# odr1_redraw.net
KiCad netlist of a schematic drawn in EAGLE
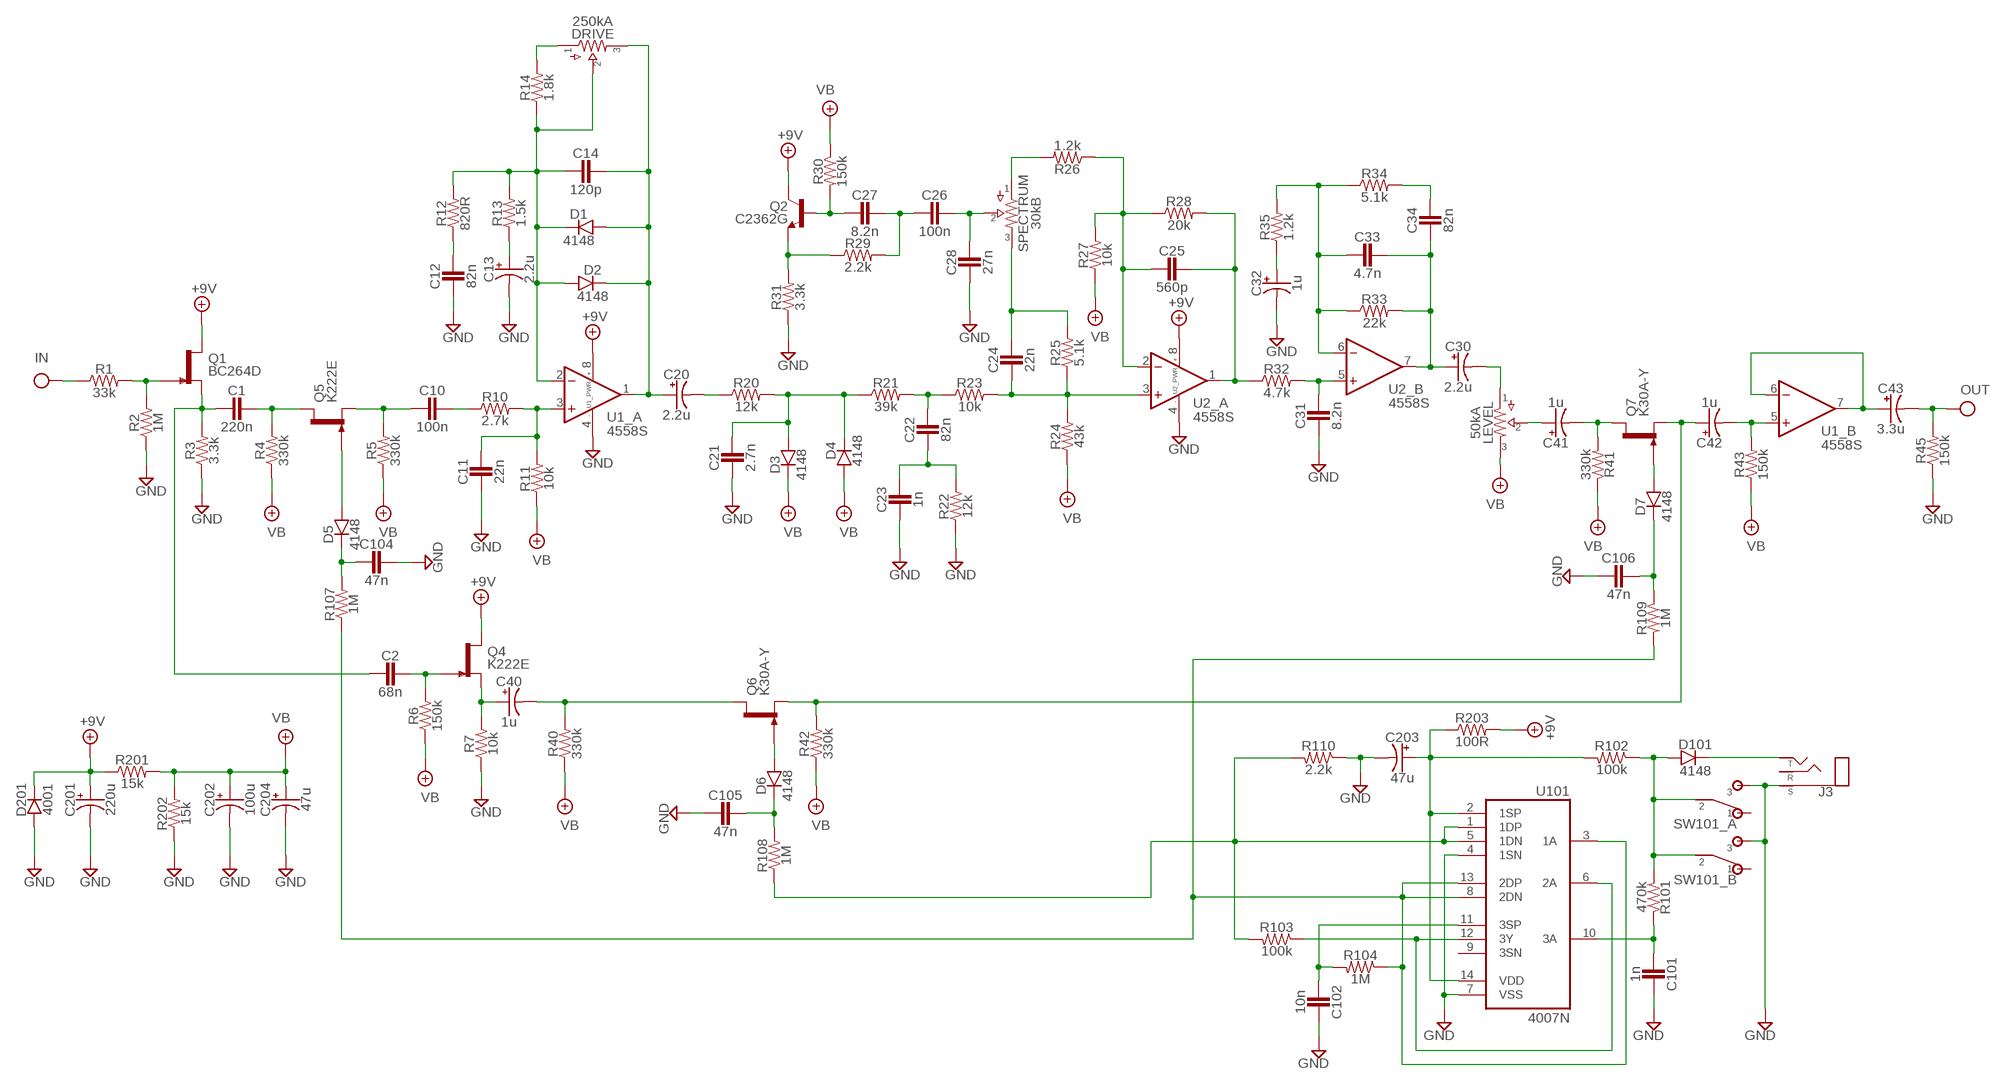
[diagram p0: schematic, sheet 1]

(export (version "E")
  (design (tool "Eeschema 10.0.6"))
  (components
    (comp (ref "C1")
      (value "220n")
      (footprint "eagle-import:BOX_SMALL")
      (libsource (lib "eagle-import") (part "CER/FILMBOX.1"))
    )
    (comp (ref "C2")
      (value "68n")
      (footprint "eagle-import:BOX_SMALL")
      (libsource (lib "eagle-import") (part "CER/FILMBOX.1"))
    )
    (comp (ref "C10")
      (value "100n")
      (footprint "eagle-import:BOX_SMALL")
      (libsource (lib "eagle-import") (part "CER/FILMBOX.1"))
    )
    (comp (ref "C11")
      (value "22n")
      (footprint "eagle-import:BOX_SMALL")
      (libsource (lib "eagle-import") (part "CER/FILMBOX.1"))
    )
    (comp (ref "C12")
      (value "82n")
      (footprint "eagle-import:BOX_SMALL")
      (libsource (lib "eagle-import") (part "CER/FILMBOX.1"))
    )
    (comp (ref "C13")
      (value "2.2u")
      (footprint "eagle-import:040_020")
      (libsource (lib "eagle-import") (part "0400"))
    )
    (comp (ref "C14")
      (value "120p")
      (footprint "eagle-import:BOX_SMALL")
      (libsource (lib "eagle-import") (part "CER/FILMBOX.1"))
    )
    (comp (ref "C20")
      (value "2.2u")
      (footprint "eagle-import:040_020")
      (libsource (lib "eagle-import") (part "0400"))
    )
    (comp (ref "C21")
      (value "2.7n")
      (footprint "eagle-import:BOX_SMALL")
      (libsource (lib "eagle-import") (part "CER/FILMBOX.1"))
    )
    (comp (ref "C22")
      (value "82n")
      (footprint "eagle-import:BOX_SMALL")
      (libsource (lib "eagle-import") (part "CER/FILMBOX.1"))
    )
    (comp (ref "C23")
      (value "1n")
      (footprint "eagle-import:BOX_SMALL")
      (libsource (lib "eagle-import") (part "CER/FILMBOX.1"))
    )
    (comp (ref "C24")
      (value "22n")
      (footprint "eagle-import:BOX_SMALL")
      (libsource (lib "eagle-import") (part "CER/FILMBOX.1"))
    )
    (comp (ref "C25")
      (value "560p")
      (footprint "eagle-import:BOX_SMALL")
      (libsource (lib "eagle-import") (part "CER/FILMBOX.1"))
    )
    (comp (ref "C26")
      (value "100n")
      (footprint "eagle-import:BOX_SMALL")
      (libsource (lib "eagle-import") (part "CER/FILMBOX.1"))
    )
    (comp (ref "C27")
      (value "8.2n")
      (footprint "eagle-import:BOX_SMALL")
      (libsource (lib "eagle-import") (part "CER/FILMBOX.1"))
    )
    (comp (ref "C28")
      (value "27n")
      (footprint "eagle-import:BOX_SMALL")
      (libsource (lib "eagle-import") (part "CER/FILMBOX.1"))
    )
    (comp (ref "C30")
      (value "2.2u")
      (footprint "eagle-import:040_020")
      (libsource (lib "eagle-import") (part "0400"))
    )
    (comp (ref "C31")
      (value "8.2n")
      (footprint "eagle-import:BOX_SMALL")
      (libsource (lib "eagle-import") (part "CER/FILMBOX.1"))
    )
    (comp (ref "C32")
      (value "1u")
      (footprint "eagle-import:040_020")
      (libsource (lib "eagle-import") (part "0400"))
    )
    (comp (ref "C33")
      (value "4.7n")
      (footprint "eagle-import:BOX_SMALL")
      (libsource (lib "eagle-import") (part "CER/FILMBOX.1"))
    )
    (comp (ref "C34")
      (value "82n")
      (footprint "eagle-import:BOX_SMALL")
      (libsource (lib "eagle-import") (part "CER/FILMBOX.1"))
    )
    (comp (ref "C40")
      (value "1u")
      (footprint "eagle-import:040_020")
      (libsource (lib "eagle-import") (part "0400"))
    )
    (comp (ref "C41")
      (value "1u")
      (footprint "eagle-import:040_020")
      (libsource (lib "eagle-import") (part "0400"))
    )
    (comp (ref "C42")
      (value "1u")
      (footprint "eagle-import:040_020")
      (libsource (lib "eagle-import") (part "0400"))
    )
    (comp (ref "C43")
      (value "3.3u")
      (footprint "eagle-import:040_020")
      (libsource (lib "eagle-import") (part "0400"))
    )
    (comp (ref "C101")
      (value "1n")
      (footprint "eagle-import:BOX_SMALL")
      (libsource (lib "eagle-import") (part "CER/FILMBOX.1"))
    )
    (comp (ref "C102")
      (value "10n")
      (footprint "eagle-import:BOX_SMALL")
      (libsource (lib "eagle-import") (part "CER/FILMBOX.1"))
    )
    (comp (ref "C104")
      (value "47n")
      (footprint "eagle-import:BOX_SMALL")
      (libsource (lib "eagle-import") (part "CER/FILMBOX.1"))
    )
    (comp (ref "C105")
      (value "47n")
      (footprint "eagle-import:BOX_SMALL")
      (libsource (lib "eagle-import") (part "CER/FILMBOX.1"))
    )
    (comp (ref "C106")
      (value "47n")
      (footprint "eagle-import:BOX_SMALL")
      (libsource (lib "eagle-import") (part "CER/FILMBOX.1"))
    )
    (comp (ref "C201")
      (value "220u")
      (footprint "eagle-import:040_020")
      (libsource (lib "eagle-import") (part "0400"))
    )
    (comp (ref "C202")
      (value "100u")
      (footprint "eagle-import:040_020")
      (libsource (lib "eagle-import") (part "0400"))
    )
    (comp (ref "C203")
      (value "47u")
      (footprint "eagle-import:040_020")
      (libsource (lib "eagle-import") (part "0400"))
    )
    (comp (ref "C204")
      (value "47u")
      (footprint "eagle-import:040_020")
      (libsource (lib "eagle-import") (part "0400"))
    )
    (comp (ref "D1")
      (value "4148")
      (footprint "eagle-import:DO35-2")
      (libsource (lib "eagle-import") (part "DO35.2"))
    )
    (comp (ref "D2")
      (value "4148")
      (footprint "eagle-import:DO35-2")
      (libsource (lib "eagle-import") (part "DO35.2"))
    )
    (comp (ref "D3")
      (value "4148")
      (footprint "eagle-import:DO35-2")
      (libsource (lib "eagle-import") (part "DO35.2"))
    )
    (comp (ref "D4")
      (value "4148")
      (footprint "eagle-import:DO35-2")
      (libsource (lib "eagle-import") (part "DO35.2"))
    )
    (comp (ref "D5")
      (value "4148")
      (footprint "eagle-import:DO35-2")
      (libsource (lib "eagle-import") (part "DO35.2"))
    )
    (comp (ref "D6")
      (value "4148")
      (footprint "eagle-import:DO35-2")
      (libsource (lib "eagle-import") (part "DO35.2"))
    )
    (comp (ref "D7")
      (value "4148")
      (footprint "eagle-import:DO35-2")
      (libsource (lib "eagle-import") (part "DO35.2"))
    )
    (comp (ref "D101")
      (value "4148")
      (footprint "eagle-import:DO35-2")
      (libsource (lib "eagle-import") (part "DO35.2"))
    )
    (comp (ref "D201")
      (value "4001")
      (footprint "eagle-import:DO35-2")
      (libsource (lib "eagle-import") (part "DO35.2"))
    )
    (comp (ref "DRIVE")
      (value "250kA")
      (footprint "eagle-import:16MM")
      (libsource (lib "eagle-import") (part "POTS16MM"))
    )
    (comp (ref "J3")
      (value "STEREO3PADS")
      (footprint "eagle-import:THREEPADS")
      (libsource (lib "eagle-import") (part "STEREO3PADS"))
    )
    (comp (ref "LEVEL")
      (value "50kA")
      (footprint "eagle-import:16MM")
      (libsource (lib "eagle-import") (part "POTS16MM"))
    )
    (comp (ref "Q1")
      (value "BC264D")
      (footprint "eagle-import:TO92-")
      (libsource (lib "eagle-import") (part "2N3819TO-92S"))
    )
    (comp (ref "Q2")
      (value "C2362G")
      (footprint "eagle-import:TO92-")
      (libsource (lib "eagle-import") (part "2N3904"))
    )
    (comp (ref "Q4")
      (value "K222E")
      (footprint "eagle-import:TO92-")
      (libsource (lib "eagle-import") (part "2N3819TO-92S"))
    )
    (comp (ref "Q5")
      (value "K222E")
      (footprint "eagle-import:TO92-")
      (libsource (lib "eagle-import") (part "2N3819TO-92S"))
    )
    (comp (ref "Q6")
      (value "K30A-Y")
      (footprint "eagle-import:TO92-")
      (libsource (lib "eagle-import") (part "2N3819TO-92S"))
    )
    (comp (ref "Q7")
      (value "K30A-Y")
      (footprint "eagle-import:TO92-")
      (libsource (lib "eagle-import") (part "2N3819TO-92S"))
    )
    (comp (ref "R1")
      (value "33k")
      (footprint "eagle-import:R0207_3")
      (libsource (lib "eagle-import") (part "R_.3B"))
    )
    (comp (ref "R2")
      (value "1M")
      (footprint "eagle-import:R0207_3")
      (libsource (lib "eagle-import") (part "R_.3B"))
    )
    (comp (ref "R3")
      (value "3.3k")
      (footprint "eagle-import:R0207_3")
      (libsource (lib "eagle-import") (part "R_.3B"))
    )
    (comp (ref "R4")
      (value "330k")
      (footprint "eagle-import:R0207_3")
      (libsource (lib "eagle-import") (part "R_.3B"))
    )
    (comp (ref "R5")
      (value "330k")
      (footprint "eagle-import:R0207_3")
      (libsource (lib "eagle-import") (part "R_.3B"))
    )
    (comp (ref "R6")
      (value "150k")
      (footprint "eagle-import:R0207_3")
      (libsource (lib "eagle-import") (part "R_.3B"))
    )
    (comp (ref "R7")
      (value "10k")
      (footprint "eagle-import:R0207_3")
      (libsource (lib "eagle-import") (part "R_.3B"))
    )
    (comp (ref "R10")
      (value "2.7k")
      (footprint "eagle-import:R0207_3")
      (libsource (lib "eagle-import") (part "R_.3B"))
    )
    (comp (ref "R11")
      (value "10k")
      (footprint "eagle-import:R0207_3")
      (libsource (lib "eagle-import") (part "R_.3B"))
    )
    (comp (ref "R12")
      (value "820R")
      (footprint "eagle-import:R0207_3")
      (libsource (lib "eagle-import") (part "R_.3B"))
    )
    (comp (ref "R13")
      (value "1.5k")
      (footprint "eagle-import:R0207_3")
      (libsource (lib "eagle-import") (part "R_.3B"))
    )
    (comp (ref "R14")
      (value "1.8k")
      (footprint "eagle-import:R0207_3")
      (libsource (lib "eagle-import") (part "R_.3B"))
    )
    (comp (ref "R20")
      (value "12k")
      (footprint "eagle-import:R0207_3")
      (libsource (lib "eagle-import") (part "R_.3B"))
    )
    (comp (ref "R21")
      (value "39k")
      (footprint "eagle-import:R0207_3")
      (libsource (lib "eagle-import") (part "R_.3B"))
    )
    (comp (ref "R22")
      (value "12k")
      (footprint "eagle-import:R0207_3")
      (libsource (lib "eagle-import") (part "R_.3B"))
    )
    (comp (ref "R23")
      (value "10k")
      (footprint "eagle-import:R0207_3")
      (libsource (lib "eagle-import") (part "R_.3B"))
    )
    (comp (ref "R24")
      (value "43k")
      (footprint "eagle-import:R0207_3")
      (libsource (lib "eagle-import") (part "R_.3B"))
    )
    (comp (ref "R25")
      (value "5.1k")
      (footprint "eagle-import:R0207_3")
      (libsource (lib "eagle-import") (part "R_.3B"))
    )
    (comp (ref "R26")
      (value "1.2k")
      (footprint "eagle-import:R0207_3")
      (libsource (lib "eagle-import") (part "R_.3B"))
    )
    (comp (ref "R27")
      (value "10k")
      (footprint "eagle-import:R0207_3")
      (libsource (lib "eagle-import") (part "R_.3B"))
    )
    (comp (ref "R28")
      (value "20k")
      (footprint "eagle-import:R0207_3")
      (libsource (lib "eagle-import") (part "R_.3B"))
    )
    (comp (ref "R29")
      (value "2.2k")
      (footprint "eagle-import:R0207_3")
      (libsource (lib "eagle-import") (part "R_.3B"))
    )
    (comp (ref "R30")
      (value "150k")
      (footprint "eagle-import:R0207_3")
      (libsource (lib "eagle-import") (part "R_.3B"))
    )
    (comp (ref "R31")
      (value "3.3k")
      (footprint "eagle-import:R0207_3")
      (libsource (lib "eagle-import") (part "R_.3B"))
    )
    (comp (ref "R32")
      (value "4.7k")
      (footprint "eagle-import:R0207_3")
      (libsource (lib "eagle-import") (part "R_.3B"))
    )
    (comp (ref "R33")
      (value "22k")
      (footprint "eagle-import:R0207_3")
      (libsource (lib "eagle-import") (part "R_.3B"))
    )
    (comp (ref "R34")
      (value "5.1k")
      (footprint "eagle-import:R0207_3")
      (libsource (lib "eagle-import") (part "R_.3B"))
    )
    (comp (ref "R35")
      (value "1.2k")
      (footprint "eagle-import:R0207_3")
      (libsource (lib "eagle-import") (part "R_.3B"))
    )
    (comp (ref "R40")
      (value "330k")
      (footprint "eagle-import:R0207_3")
      (libsource (lib "eagle-import") (part "R_.3B"))
    )
    (comp (ref "R41")
      (value "330k")
      (footprint "eagle-import:R0207_3")
      (libsource (lib "eagle-import") (part "R_.3B"))
    )
    (comp (ref "R42")
      (value "330k")
      (footprint "eagle-import:R0207_3")
      (libsource (lib "eagle-import") (part "R_.3B"))
    )
    (comp (ref "R43")
      (value "150k")
      (footprint "eagle-import:R0207_3")
      (libsource (lib "eagle-import") (part "R_.3B"))
    )
    (comp (ref "R45")
      (value "150k")
      (footprint "eagle-import:R0207_3")
      (libsource (lib "eagle-import") (part "R_.3B"))
    )
    (comp (ref "R101")
      (value "470k")
      (footprint "eagle-import:R0207_3")
      (libsource (lib "eagle-import") (part "R_.3B"))
    )
    (comp (ref "R102")
      (value "100k")
      (footprint "eagle-import:R0207_3")
      (libsource (lib "eagle-import") (part "R_.3B"))
    )
    (comp (ref "R103")
      (value "100k")
      (footprint "eagle-import:R0207_3")
      (libsource (lib "eagle-import") (part "R_.3B"))
    )
    (comp (ref "R104")
      (value "1M")
      (footprint "eagle-import:R0207_3")
      (libsource (lib "eagle-import") (part "R_.3B"))
    )
    (comp (ref "R107")
      (value "1M")
      (footprint "eagle-import:R0207_3")
      (libsource (lib "eagle-import") (part "R_.3B"))
    )
    (comp (ref "R108")
      (value "1M")
      (footprint "eagle-import:R0207_3")
      (libsource (lib "eagle-import") (part "R_.3B"))
    )
    (comp (ref "R109")
      (value "1M")
      (footprint "eagle-import:R0207_3")
      (libsource (lib "eagle-import") (part "R_.3B"))
    )
    (comp (ref "R110")
      (value "2.2k")
      (footprint "eagle-import:R0207_3")
      (libsource (lib "eagle-import") (part "R_.3B"))
    )
    (comp (ref "R201")
      (value "15k")
      (footprint "eagle-import:R0207_3")
      (libsource (lib "eagle-import") (part "R_.3B"))
    )
    (comp (ref "R202")
      (value "15k")
      (footprint "eagle-import:R0207_3")
      (libsource (lib "eagle-import") (part "R_.3B"))
    )
    (comp (ref "R203")
      (value "100R")
      (footprint "eagle-import:R0207_3")
      (libsource (lib "eagle-import") (part "R_.3B"))
    )
    (comp (ref "SPECTRUM")
      (value "30kB")
      (footprint "eagle-import:16MM")
      (libsource (lib "eagle-import") (part "POTS16MM"))
    )
    (comp (ref "SW101")
      (value "DPDT")
      (footprint "eagle-import:DPDT")
      (libsource (lib "eagle-import") (part "DPDT"))
    )
    (comp (ref "U1")
      (value "4558S")
      (footprint "eagle-import:DIL0")
      (libsource (lib "eagle-import") (part "DUALTH"))
    )
    (comp (ref "U2")
      (value "4558S")
      (footprint "eagle-import:DIL0")
      (libsource (lib "eagle-import") (part "DUALTH"))
    )
    (comp (ref "U101")
      (value "4007N")
      (footprint "eagle-import:DIL14")
      (libsource (lib "eagle-import") (part "4007N"))
    )
  )
  (nets
    (net (code "1") (name "+9V") (class "Default")
      (node (ref "C201") (pin "+") (pinfunction "+_+") (pintype "passive"))
      (node (ref "D201") (pin "C") (pinfunction "C_C") (pintype "passive"))
      (node (ref "Q1") (pin "3") (pinfunction "D_3") (pintype "passive"))
      (node (ref "Q2") (pin "1") (pinfunction "C_1") (pintype "passive"))
      (node (ref "Q4") (pin "3") (pinfunction "D_3") (pintype "passive"))
      (node (ref "R201") (pin "1") (pinfunction "1_1") (pintype "passive"))
      (node (ref "R203") (pin "2") (pinfunction "2_2") (pintype "passive"))
      (node (ref "U1") (pin "8") (pinfunction "V+_8") (pintype "power_in"))
      (node (ref "U2") (pin "8") (pinfunction "V+_8") (pintype "power_in"))
    )
    (net (code "2") (name "GND") (class "Default")
      (node (ref "C101") (pin "2") (pinfunction "2_2") (pintype "passive"))
      (node (ref "C102") (pin "2") (pinfunction "2_2") (pintype "passive"))
      (node (ref "C104") (pin "2") (pinfunction "2_2") (pintype "passive"))
      (node (ref "C105") (pin "2") (pinfunction "2_2") (pintype "passive"))
      (node (ref "C106") (pin "2") (pinfunction "2_2") (pintype "passive"))
      (node (ref "C11") (pin "2") (pinfunction "2_2") (pintype "passive"))
      (node (ref "C12") (pin "2") (pinfunction "2_2") (pintype "passive"))
      (node (ref "C13") (pin "-") (pinfunction "-_-") (pintype "passive"))
      (node (ref "C201") (pin "-") (pinfunction "-_-") (pintype "passive"))
      (node (ref "C202") (pin "-") (pinfunction "-_-") (pintype "passive"))
      (node (ref "C203") (pin "-") (pinfunction "-_-") (pintype "passive"))
      (node (ref "C204") (pin "-") (pinfunction "-_-") (pintype "passive"))
      (node (ref "C21") (pin "2") (pinfunction "2_2") (pintype "passive"))
      (node (ref "C23") (pin "2") (pinfunction "2_2") (pintype "passive"))
      (node (ref "C28") (pin "2") (pinfunction "2_2") (pintype "passive"))
      (node (ref "C31") (pin "2") (pinfunction "2_2") (pintype "passive"))
      (node (ref "C32") (pin "-") (pinfunction "-_-") (pintype "passive"))
      (node (ref "D201") (pin "A") (pinfunction "A_A") (pintype "passive"))
      (node (ref "J3") (pin "SLEEVE") (pinfunction "S_SLEEVE") (pintype "passive"))
      (node (ref "R110") (pin "1") (pinfunction "1_1") (pintype "passive"))
      (node (ref "R2") (pin "1") (pinfunction "1_1") (pintype "passive"))
      (node (ref "R202") (pin "1") (pinfunction "1_1") (pintype "passive"))
      (node (ref "R22") (pin "1") (pinfunction "1_1") (pintype "passive"))
      (node (ref "R3") (pin "1") (pinfunction "1_1") (pintype "passive"))
      (node (ref "R31") (pin "1") (pinfunction "1_1") (pintype "passive"))
      (node (ref "R45") (pin "1") (pinfunction "1_1") (pintype "passive"))
      (node (ref "R7") (pin "1") (pinfunction "1_1") (pintype "passive"))
      (node (ref "SW101") (pin "A3") (pinfunction "3_A3") (pintype "passive"))
      (node (ref "SW101") (pin "B3") (pinfunction "3_B3") (pintype "passive"))
      (node (ref "U1") (pin "4") (pinfunction "V-_4") (pintype "power_in"))
      (node (ref "U101") (pin "4") (pinfunction "1SN_4") (pintype "open_collector"))
      (node (ref "U101") (pin "7") (pinfunction "VSS_7") (pintype "input"))
      (node (ref "U2") (pin "4") (pinfunction "V-_4") (pintype "power_in"))
    )
    (net (code "3") (name "IN") (class "Default")
      (node (ref "R1") (pin "1") (pinfunction "1_1") (pintype "passive"))
    )
    (net (code "4") (name "Net-(C10-Pad1)") (class "Default")
      (node (ref "C10") (pin "1") (pinfunction "1_1") (pintype "passive"))
      (node (ref "R10") (pin "1") (pinfunction "1_1") (pintype "passive"))
    )
    (net (code "5") (name "Net-(C12-Pad1)") (class "Default")
      (node (ref "C12") (pin "1") (pinfunction "1_1") (pintype "passive"))
      (node (ref "R12") (pin "1") (pinfunction "1_1") (pintype "passive"))
    )
    (net (code "6") (name "Net-(C13-Pad+)") (class "Default")
      (node (ref "C13") (pin "+") (pinfunction "+_+") (pintype "passive"))
      (node (ref "R13") (pin "1") (pinfunction "1_1") (pintype "passive"))
    )
    (net (code "7") (name "Net-(C20-Pad-)") (class "Default")
      (node (ref "C20") (pin "-") (pinfunction "-_-") (pintype "passive"))
      (node (ref "R20") (pin "1") (pinfunction "1_1") (pintype "passive"))
    )
    (net (code "8") (name "Net-(C21-Pad1)") (class "Default")
      (node (ref "C21") (pin "1") (pinfunction "1_1") (pintype "passive"))
      (node (ref "D3") (pin "A") (pinfunction "A_A") (pintype "passive"))
      (node (ref "D4") (pin "C") (pinfunction "C_C") (pintype "passive"))
      (node (ref "R20") (pin "2") (pinfunction "2_2") (pintype "passive"))
      (node (ref "R21") (pin "1") (pinfunction "1_1") (pintype "passive"))
    )
    (net (code "9") (name "Net-(C22-Pad1)") (class "Default")
      (node (ref "C22") (pin "1") (pinfunction "1_1") (pintype "passive"))
      (node (ref "R21") (pin "2") (pinfunction "2_2") (pintype "passive"))
      (node (ref "R23") (pin "1") (pinfunction "1_1") (pintype "passive"))
    )
    (net (code "10") (name "Net-(C22-Pad2)") (class "Default")
      (node (ref "C22") (pin "2") (pinfunction "2_2") (pintype "passive"))
      (node (ref "C23") (pin "1") (pinfunction "1_1") (pintype "passive"))
      (node (ref "R22") (pin "2") (pinfunction "2_2") (pintype "passive"))
    )
    (net (code "11") (name "Net-(C24-Pad1)") (class "Default")
      (node (ref "C24") (pin "1") (pinfunction "1_1") (pintype "passive"))
      (node (ref "R25") (pin "2") (pinfunction "2_2") (pintype "passive"))
      (node (ref "SPECTRUM") (pin "3") (pinfunction "3_3") (pintype "passive"))
    )
    (net (code "12") (name "Net-(C26-Pad1)") (class "Default")
      (node (ref "C26") (pin "1") (pinfunction "1_1") (pintype "passive"))
      (node (ref "C28") (pin "1") (pinfunction "1_1") (pintype "passive"))
      (node (ref "SPECTRUM") (pin "2") (pinfunction "2_2") (pintype "passive"))
    )
    (net (code "13") (name "Net-(C26-Pad2)") (class "Default")
      (node (ref "C26") (pin "2") (pinfunction "2_2") (pintype "passive"))
      (node (ref "C27") (pin "1") (pinfunction "1_1") (pintype "passive"))
      (node (ref "R29") (pin "2") (pinfunction "2_2") (pintype "passive"))
    )
    (net (code "14") (name "Net-(C30-Pad-)") (class "Default")
      (node (ref "C30") (pin "-") (pinfunction "-_-") (pintype "passive"))
      (node (ref "LEVEL") (pin "1") (pinfunction "1_1") (pintype "passive"))
    )
    (net (code "15") (name "Net-(C32-Pad+)") (class "Default")
      (node (ref "C32") (pin "+") (pinfunction "+_+") (pintype "passive"))
      (node (ref "R35") (pin "1") (pinfunction "1_1") (pintype "passive"))
    )
    (net (code "16") (name "Net-(C34-Pad1)") (class "Default")
      (node (ref "C34") (pin "1") (pinfunction "1_1") (pintype "passive"))
      (node (ref "R34") (pin "2") (pinfunction "2_2") (pintype "passive"))
    )
    (net (code "17") (name "Net-(C41-Pad+)") (class "Default")
      (node (ref "C41") (pin "+") (pinfunction "+_+") (pintype "passive"))
      (node (ref "LEVEL") (pin "2") (pinfunction "2_2") (pintype "passive"))
    )
    (net (code "18") (name "Net-(C104-Pad1)") (class "Default")
      (node (ref "C104") (pin "1") (pinfunction "1_1") (pintype "passive"))
      (node (ref "D5") (pin "C") (pinfunction "C_C") (pintype "passive"))
      (node (ref "R107") (pin "2") (pinfunction "2_2") (pintype "passive"))
    )
    (net (code "19") (name "Net-(C105-Pad1)") (class "Default")
      (node (ref "C105") (pin "1") (pinfunction "1_1") (pintype "passive"))
      (node (ref "D6") (pin "C") (pinfunction "C_C") (pintype "passive"))
      (node (ref "R108") (pin "2") (pinfunction "2_2") (pintype "passive"))
    )
    (net (code "20") (name "Net-(C106-Pad1)") (class "Default")
      (node (ref "C106") (pin "1") (pinfunction "1_1") (pintype "passive"))
      (node (ref "D7") (pin "C") (pinfunction "C_C") (pintype "passive"))
      (node (ref "R109") (pin "1") (pinfunction "1_1") (pintype "passive"))
    )
    (net (code "21") (name "Net-(DRIVE-Pad1)") (class "Default")
      (node (ref "DRIVE") (pin "1") (pinfunction "1_1") (pintype "passive"))
      (node (ref "R14") (pin "2") (pinfunction "2_2") (pintype "passive"))
    )
    (net (code "22") (name "Net-(J3-T)") (class "Default")
      (node (ref "D101") (pin "C") (pinfunction "C_C") (pintype "passive"))
      (node (ref "J3") (pin "TIP") (pinfunction "T_TIP") (pintype "passive"))
    )
    (net (code "23") (name "Net-(Q1-G)") (class "Default")
      (node (ref "Q1") (pin "2") (pinfunction "G_2") (pintype "passive"))
      (node (ref "R1") (pin "2") (pinfunction "2_2") (pintype "passive"))
      (node (ref "R2") (pin "2") (pinfunction "2_2") (pintype "passive"))
    )
    (net (code "24") (name "Net-(Q1-S)") (class "Default")
      (node (ref "C1") (pin "2") (pinfunction "2_2") (pintype "passive"))
      (node (ref "C2") (pin "2") (pinfunction "2_2") (pintype "passive"))
      (node (ref "Q1") (pin "1") (pinfunction "S_1") (pintype "passive"))
      (node (ref "R3") (pin "2") (pinfunction "2_2") (pintype "passive"))
    )
    (net (code "25") (name "Net-(Q2-B)") (class "Default")
      (node (ref "C27") (pin "2") (pinfunction "2_2") (pintype "passive"))
      (node (ref "Q2") (pin "2") (pinfunction "B_2") (pintype "passive"))
      (node (ref "R30") (pin "2") (pinfunction "2_2") (pintype "passive"))
    )
    (net (code "26") (name "Net-(Q2-E)") (class "Default")
      (node (ref "Q2") (pin "3") (pinfunction "E_3") (pintype "passive"))
      (node (ref "R29") (pin "1") (pinfunction "1_1") (pintype "passive"))
      (node (ref "R31") (pin "2") (pinfunction "2_2") (pintype "passive"))
    )
    (net (code "27") (name "Net-(Q4-G)") (class "Default")
      (node (ref "C2") (pin "1") (pinfunction "1_1") (pintype "passive"))
      (node (ref "Q4") (pin "2") (pinfunction "G_2") (pintype "passive"))
      (node (ref "R6") (pin "2") (pinfunction "2_2") (pintype "passive"))
    )
    (net (code "28") (name "Net-(Q4-S)") (class "Default")
      (node (ref "C40") (pin "+") (pinfunction "+_+") (pintype "passive"))
      (node (ref "Q4") (pin "1") (pinfunction "S_1") (pintype "passive"))
      (node (ref "R7") (pin "2") (pinfunction "2_2") (pintype "passive"))
    )
    (net (code "29") (name "Net-(Q5-D)") (class "Default")
      (node (ref "C1") (pin "1") (pinfunction "1_1") (pintype "passive"))
      (node (ref "Q5") (pin "3") (pinfunction "D_3") (pintype "passive"))
      (node (ref "R4") (pin "2") (pinfunction "2_2") (pintype "passive"))
    )
    (net (code "30") (name "Net-(Q5-G)") (class "Default")
      (node (ref "D5") (pin "A") (pinfunction "A_A") (pintype "passive"))
      (node (ref "Q5") (pin "2") (pinfunction "G_2") (pintype "passive"))
    )
    (net (code "31") (name "Net-(Q5-S)") (class "Default")
      (node (ref "C10") (pin "2") (pinfunction "2_2") (pintype "passive"))
      (node (ref "Q5") (pin "1") (pinfunction "S_1") (pintype "passive"))
      (node (ref "R5") (pin "2") (pinfunction "2_2") (pintype "passive"))
    )
    (net (code "32") (name "Net-(Q6-D)") (class "Default")
      (node (ref "C40") (pin "-") (pinfunction "-_-") (pintype "passive"))
      (node (ref "Q6") (pin "3") (pinfunction "D_3") (pintype "passive"))
      (node (ref "R40") (pin "2") (pinfunction "2_2") (pintype "passive"))
    )
    (net (code "33") (name "Net-(Q6-G)") (class "Default")
      (node (ref "D6") (pin "A") (pinfunction "A_A") (pintype "passive"))
      (node (ref "Q6") (pin "2") (pinfunction "G_2") (pintype "passive"))
    )
    (net (code "34") (name "Net-(Q6-S)") (class "Default")
      (node (ref "C42") (pin "+") (pinfunction "+_+") (pintype "passive"))
      (node (ref "Q6") (pin "1") (pinfunction "S_1") (pintype "passive"))
      (node (ref "Q7") (pin "1") (pinfunction "S_1") (pintype "passive"))
      (node (ref "R42") (pin "2") (pinfunction "2_2") (pintype "passive"))
    )
    (net (code "35") (name "Net-(Q7-D)") (class "Default")
      (node (ref "C41") (pin "-") (pinfunction "-_-") (pintype "passive"))
      (node (ref "Q7") (pin "3") (pinfunction "D_3") (pintype "passive"))
      (node (ref "R41") (pin "2") (pinfunction "2_2") (pintype "passive"))
    )
    (net (code "36") (name "Net-(Q7-G)") (class "Default")
      (node (ref "D7") (pin "A") (pinfunction "A_A") (pintype "passive"))
      (node (ref "Q7") (pin "2") (pinfunction "G_2") (pintype "passive"))
    )
    (net (code "37") (name "Net-(R26-Pad2)") (class "Default")
      (node (ref "R26") (pin "2") (pinfunction "2_2") (pintype "passive"))
      (node (ref "SPECTRUM") (pin "1") (pinfunction "1_1") (pintype "passive"))
    )
    (net (code "38") (name "Net-(SW101A-2)") (class "Default")
      (node (ref "D101") (pin "A") (pinfunction "A_A") (pintype "passive"))
      (node (ref "R101") (pin "2") (pinfunction "2_2") (pintype "passive"))
      (node (ref "R102") (pin "1") (pinfunction "1_1") (pintype "passive"))
      (node (ref "SW101") (pin "A2") (pinfunction "2_A2") (pintype "passive"))
      (node (ref "SW101") (pin "B2") (pinfunction "2_B2") (pintype "passive"))
    )
    (net (code "39") (name "Net-(U1A-+IN)") (class "Default")
      (node (ref "C11") (pin "1") (pinfunction "1_1") (pintype "passive"))
      (node (ref "R10") (pin "2") (pinfunction "2_2") (pintype "passive"))
      (node (ref "R11") (pin "2") (pinfunction "2_2") (pintype "passive"))
      (node (ref "U1") (pin "3") (pinfunction "+IN_3") (pintype "input"))
    )
    (net (code "40") (name "Net-(U1A--IN)") (class "Default")
      (node (ref "C14") (pin "2") (pinfunction "2_2") (pintype "passive"))
      (node (ref "D1") (pin "C") (pinfunction "C_C") (pintype "passive"))
      (node (ref "D2") (pin "A") (pinfunction "A_A") (pintype "passive"))
      (node (ref "DRIVE") (pin "2") (pinfunction "2_2") (pintype "passive"))
      (node (ref "R12") (pin "2") (pinfunction "2_2") (pintype "passive"))
      (node (ref "R13") (pin "2") (pinfunction "2_2") (pintype "passive"))
      (node (ref "R14") (pin "1") (pinfunction "1_1") (pintype "passive"))
      (node (ref "U1") (pin "2") (pinfunction "-IN_2") (pintype "input"))
    )
    (net (code "41") (name "Net-(U1A-OUT)") (class "Default")
      (node (ref "C14") (pin "1") (pinfunction "1_1") (pintype "passive"))
      (node (ref "C20") (pin "+") (pinfunction "+_+") (pintype "passive"))
      (node (ref "D1") (pin "A") (pinfunction "A_A") (pintype "passive"))
      (node (ref "D2") (pin "C") (pinfunction "C_C") (pintype "passive"))
      (node (ref "DRIVE") (pin "3") (pinfunction "3_3") (pintype "passive"))
      (node (ref "U1") (pin "1") (pinfunction "OUT_1") (pintype "output"))
    )
    (net (code "42") (name "Net-(U1B-+IN)") (class "Default")
      (node (ref "C42") (pin "-") (pinfunction "-_-") (pintype "passive"))
      (node (ref "R43") (pin "2") (pinfunction "2_2") (pintype "passive"))
      (node (ref "U1") (pin "5") (pinfunction "+IN_5") (pintype "input"))
    )
    (net (code "43") (name "Net-(U1B--IN)") (class "Default")
      (node (ref "C43") (pin "+") (pinfunction "+_+") (pintype "passive"))
      (node (ref "U1") (pin "6") (pinfunction "-IN_6") (pintype "input"))
      (node (ref "U1") (pin "7") (pinfunction "OUT_7") (pintype "output"))
    )
    (net (code "44") (name "Net-(U2A-+IN)") (class "Default")
      (node (ref "C24") (pin "2") (pinfunction "2_2") (pintype "passive"))
      (node (ref "R23") (pin "2") (pinfunction "2_2") (pintype "passive"))
      (node (ref "R24") (pin "2") (pinfunction "2_2") (pintype "passive"))
      (node (ref "R25") (pin "1") (pinfunction "1_1") (pintype "passive"))
      (node (ref "U2") (pin "3") (pinfunction "+IN_3") (pintype "input"))
    )
    (net (code "45") (name "Net-(U2A--IN)") (class "Default")
      (node (ref "C25") (pin "2") (pinfunction "2_2") (pintype "passive"))
      (node (ref "R26") (pin "1") (pinfunction "1_1") (pintype "passive"))
      (node (ref "R27") (pin "2") (pinfunction "2_2") (pintype "passive"))
      (node (ref "R28") (pin "1") (pinfunction "1_1") (pintype "passive"))
      (node (ref "U2") (pin "2") (pinfunction "-IN_2") (pintype "input"))
    )
    (net (code "46") (name "Net-(U2A-OUT)") (class "Default")
      (node (ref "C25") (pin "1") (pinfunction "1_1") (pintype "passive"))
      (node (ref "R28") (pin "2") (pinfunction "2_2") (pintype "passive"))
      (node (ref "R32") (pin "1") (pinfunction "1_1") (pintype "passive"))
      (node (ref "U2") (pin "1") (pinfunction "OUT_1") (pintype "output"))
    )
    (net (code "47") (name "Net-(U2B-+IN)") (class "Default")
      (node (ref "C31") (pin "1") (pinfunction "1_1") (pintype "passive"))
      (node (ref "R32") (pin "2") (pinfunction "2_2") (pintype "passive"))
      (node (ref "U2") (pin "5") (pinfunction "+IN_5") (pintype "input"))
    )
    (net (code "48") (name "Net-(U2B--IN)") (class "Default")
      (node (ref "C33") (pin "2") (pinfunction "2_2") (pintype "passive"))
      (node (ref "R33") (pin "1") (pinfunction "1_1") (pintype "passive"))
      (node (ref "R34") (pin "1") (pinfunction "1_1") (pintype "passive"))
      (node (ref "R35") (pin "2") (pinfunction "2_2") (pintype "passive"))
      (node (ref "U2") (pin "6") (pinfunction "-IN_6") (pintype "input"))
    )
    (net (code "49") (name "Net-(U2B-OUT)") (class "Default")
      (node (ref "C30") (pin "+") (pinfunction "+_+") (pintype "passive"))
      (node (ref "C33") (pin "1") (pinfunction "1_1") (pintype "passive"))
      (node (ref "C34") (pin "2") (pinfunction "2_2") (pintype "passive"))
      (node (ref "R33") (pin "2") (pinfunction "2_2") (pintype "passive"))
      (node (ref "U2") (pin "7") (pinfunction "OUT_7") (pintype "output"))
    )
    (net (code "50") (name "Net-(U101-1A)") (class "Default")
      (node (ref "R104") (pin "1") (pinfunction "1_1") (pintype "passive"))
      (node (ref "R107") (pin "1") (pinfunction "1_1") (pintype "passive"))
      (node (ref "R109") (pin "2") (pinfunction "2_2") (pintype "passive"))
      (node (ref "U101") (pin "13") (pinfunction "2DP_13") (pintype "bidirectional"))
      (node (ref "U101") (pin "3") (pinfunction "1A_3") (pintype "input"))
      (node (ref "U101") (pin "8") (pinfunction "2DN_8") (pintype "bidirectional"))
    )
    (net (code "51") (name "Net-(U101-1DN)") (class "Default")
      (node (ref "R103") (pin "2") (pinfunction "2_2") (pintype "passive"))
      (node (ref "R108") (pin "1") (pinfunction "1_1") (pintype "passive"))
      (node (ref "R110") (pin "2") (pinfunction "2_2") (pintype "passive"))
      (node (ref "U101") (pin "1") (pinfunction "1DP_1") (pintype "open_collector"))
      (node (ref "U101") (pin "5") (pinfunction "1DN_5") (pintype "open_collector"))
    )
    (net (code "52") (name "Net-(U101-1SP)") (class "Default")
      (node (ref "C203") (pin "+") (pinfunction "+_+") (pintype "passive"))
      (node (ref "R102") (pin "2") (pinfunction "2_2") (pintype "passive"))
      (node (ref "R203") (pin "1") (pinfunction "1_1") (pintype "passive"))
      (node (ref "U101") (pin "14") (pinfunction "VDD_14") (pintype "input"))
      (node (ref "U101") (pin "2") (pinfunction "1SP_2") (pintype "open_collector"))
    )
    (net (code "53") (name "Net-(U101-2A)") (class "Default")
      (node (ref "R103") (pin "1") (pinfunction "1_1") (pintype "passive"))
      (node (ref "U101") (pin "12") (pinfunction "3Y_12") (pintype "bidirectional"))
      (node (ref "U101") (pin "6") (pinfunction "2A_6") (pintype "input"))
    )
    (net (code "54") (name "Net-(U101-3A)") (class "Default")
      (node (ref "C101") (pin "1") (pinfunction "1_1") (pintype "passive"))
      (node (ref "R101") (pin "1") (pinfunction "1_1") (pintype "passive"))
      (node (ref "U101") (pin "10") (pinfunction "3A_10") (pintype "input"))
    )
    (net (code "55") (name "Net-(U101-3SP)") (class "Default")
      (node (ref "C102") (pin "1") (pinfunction "1_1") (pintype "passive"))
      (node (ref "R104") (pin "2") (pinfunction "2_2") (pintype "passive"))
      (node (ref "U101") (pin "11") (pinfunction "3SP_11") (pintype "bidirectional"))
    )
    (net (code "56") (name "OUT") (class "Default")
      (node (ref "C43") (pin "-") (pinfunction "-_-") (pintype "passive"))
      (node (ref "R45") (pin "2") (pinfunction "2_2") (pintype "passive"))
    )
    (net (code "57") (name "VB") (class "Default")
      (node (ref "C202") (pin "+") (pinfunction "+_+") (pintype "passive"))
      (node (ref "C204") (pin "+") (pinfunction "+_+") (pintype "passive"))
      (node (ref "D3") (pin "C") (pinfunction "C_C") (pintype "passive"))
      (node (ref "D4") (pin "A") (pinfunction "A_A") (pintype "passive"))
      (node (ref "LEVEL") (pin "3") (pinfunction "3_3") (pintype "passive"))
      (node (ref "R11") (pin "1") (pinfunction "1_1") (pintype "passive"))
      (node (ref "R201") (pin "2") (pinfunction "2_2") (pintype "passive"))
      (node (ref "R202") (pin "2") (pinfunction "2_2") (pintype "passive"))
      (node (ref "R24") (pin "1") (pinfunction "1_1") (pintype "passive"))
      (node (ref "R27") (pin "1") (pinfunction "1_1") (pintype "passive"))
      (node (ref "R30") (pin "1") (pinfunction "1_1") (pintype "passive"))
      (node (ref "R4") (pin "1") (pinfunction "1_1") (pintype "passive"))
      (node (ref "R40") (pin "1") (pinfunction "1_1") (pintype "passive"))
      (node (ref "R41") (pin "1") (pinfunction "1_1") (pintype "passive"))
      (node (ref "R42") (pin "1") (pinfunction "1_1") (pintype "passive"))
      (node (ref "R43") (pin "1") (pinfunction "1_1") (pintype "passive"))
      (node (ref "R5") (pin "1") (pinfunction "1_1") (pintype "passive"))
      (node (ref "R6") (pin "1") (pinfunction "1_1") (pintype "passive"))
    )
    (net (code "58") (name "unconnected-(J3-R-PadRING)") (class "Default")
      (node (ref "J3") (pin "RING") (pinfunction "R_RING") (pintype "passive"))
    )
    (net (code "59") (name "unconnected-(SW101A-1-PadA1)") (class "Default")
      (node (ref "SW101") (pin "A1") (pinfunction "1_A1") (pintype "passive"))
    )
    (net (code "60") (name "unconnected-(SW101B-1-PadB1)") (class "Default")
      (node (ref "SW101") (pin "B1") (pinfunction "1_B1") (pintype "passive"))
    )
    (net (code "61") (name "unconnected-(U101-3SN-Pad9)") (class "Default")
      (node (ref "U101") (pin "9") (pinfunction "3SN_9") (pintype "bidirectional"))
    )
  )
)
